# FAL65816_Audio.net
KiCad netlist of a schematic drawn in EAGLE
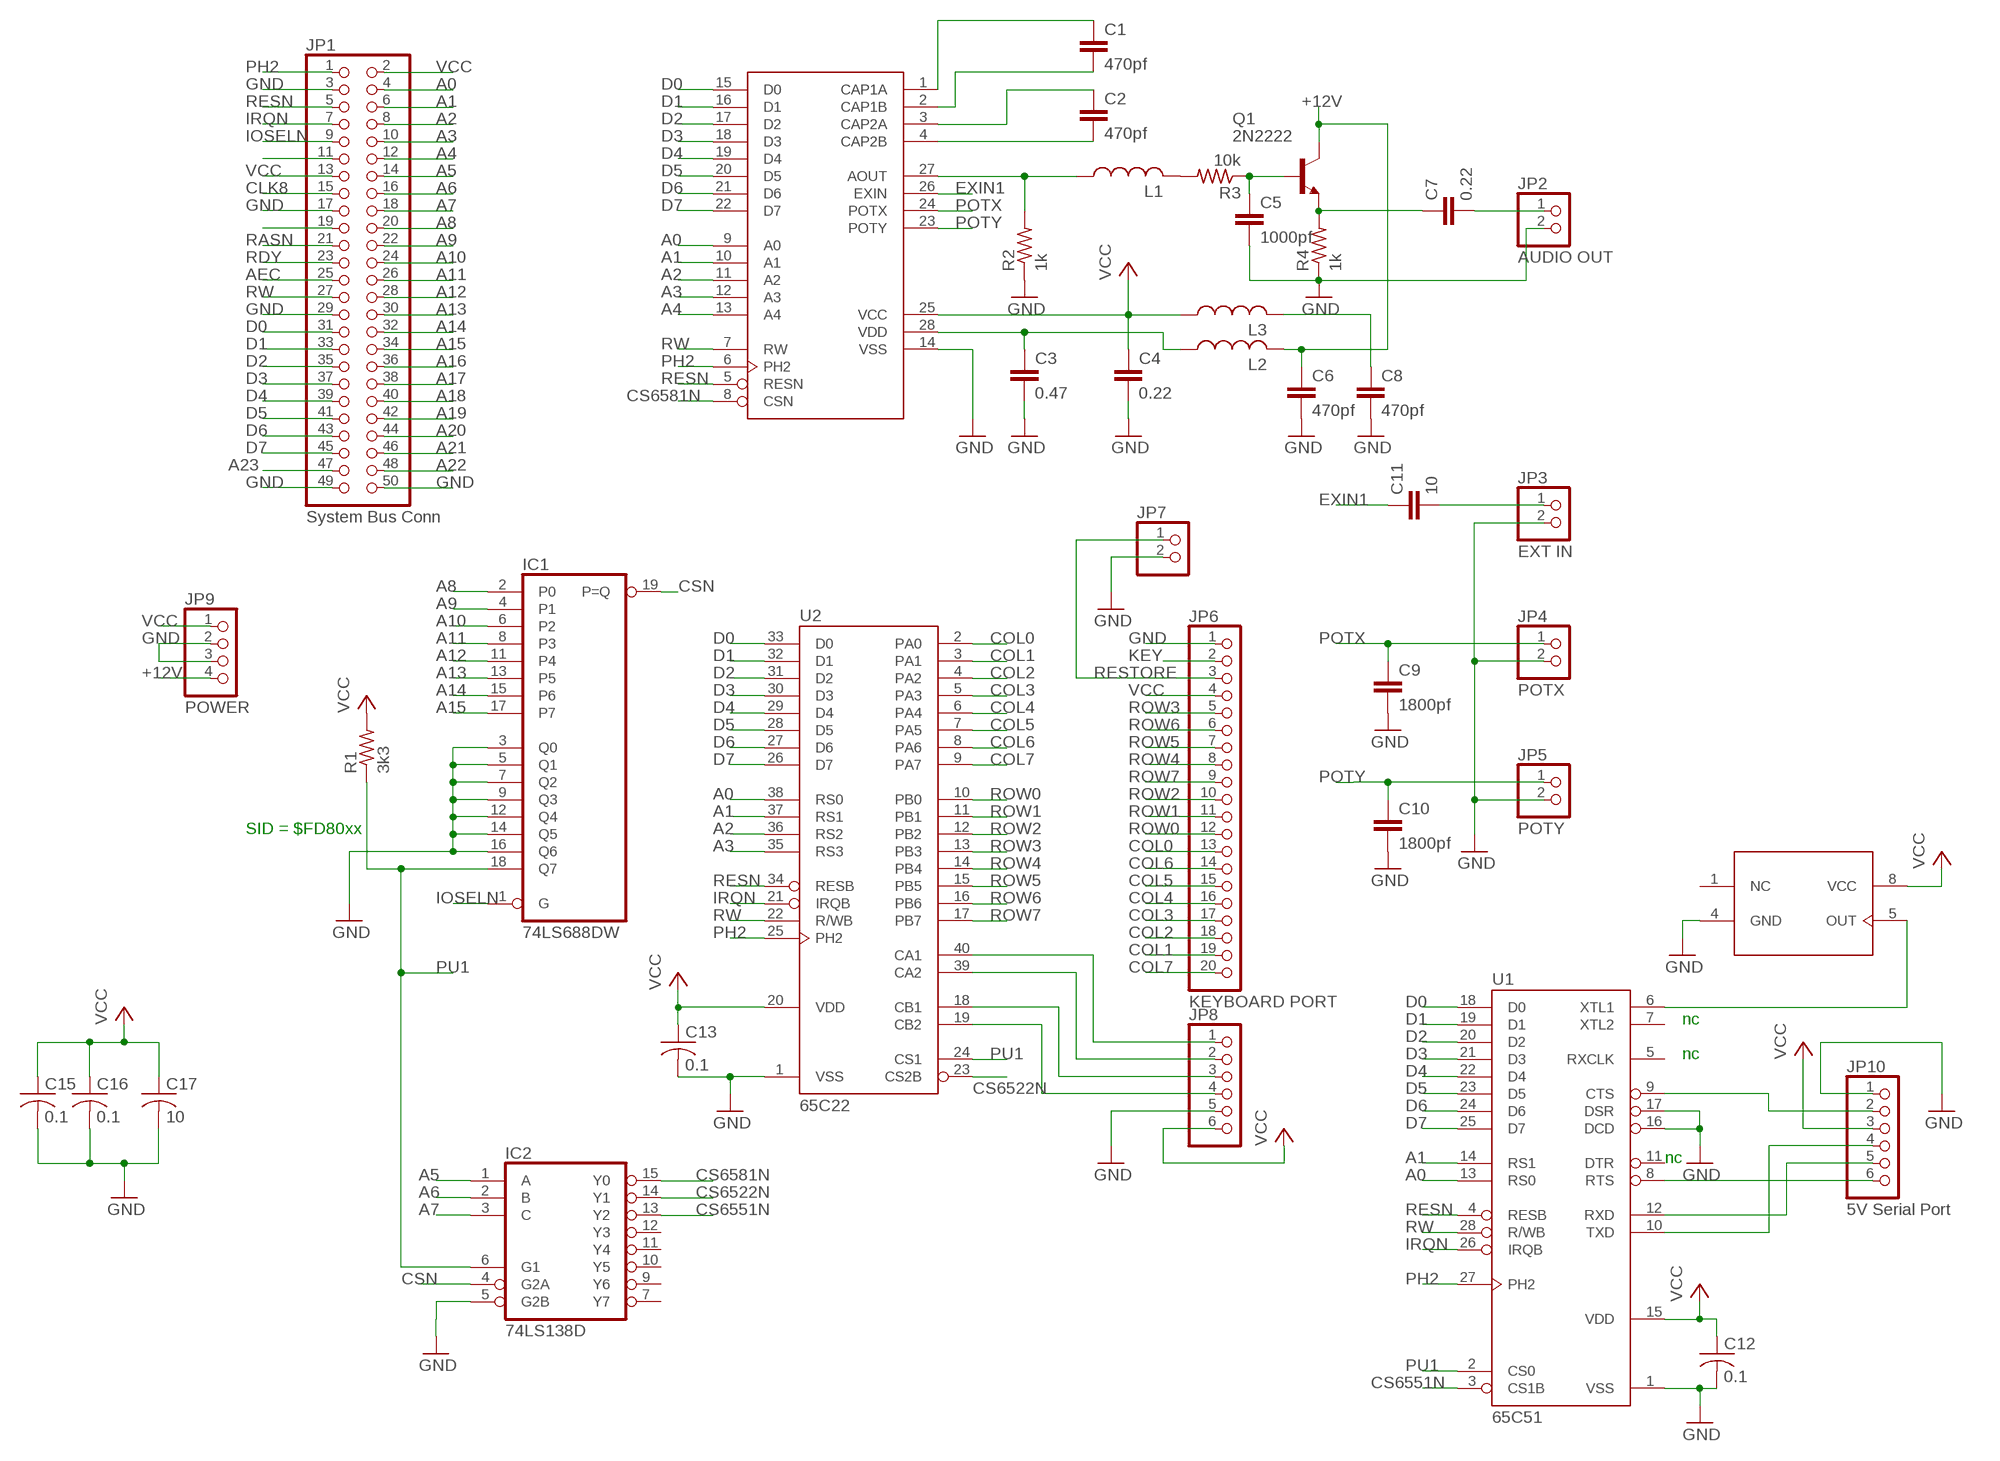
[diagram p0: schematic, sheet 1]

(export (version "E")
  (design (tool "Eeschema 10.0.6"))
  (components
    (comp (ref "C1")
      (value "470pf")
      (footprint "eagle-import:C050-024X044")
      (libsource (lib "eagle-import") (part "C-EU050-024X044"))
    )
    (comp (ref "C2")
      (value "470pf")
      (footprint "eagle-import:C050-024X044")
      (libsource (lib "eagle-import") (part "C-EU050-024X044"))
    )
    (comp (ref "C3")
      (value "0.47")
      (footprint "eagle-import:C050-024X044")
      (libsource (lib "eagle-import") (part "C-EU050-024X044"))
    )
    (comp (ref "C4")
      (value "0.22")
      (footprint "eagle-import:C050-024X044")
      (libsource (lib "eagle-import") (part "C-EU050-024X044"))
    )
    (comp (ref "C5")
      (value "1000pf")
      (footprint "eagle-import:C050-024X044")
      (libsource (lib "eagle-import") (part "C-EU050-024X044"))
    )
    (comp (ref "C6")
      (value "470pf")
      (footprint "eagle-import:C050-024X044")
      (libsource (lib "eagle-import") (part "C-EU050-024X044"))
    )
    (comp (ref "C7")
      (value "0.22")
      (footprint "eagle-import:C050-024X044")
      (libsource (lib "eagle-import") (part "C-EU050-024X044"))
    )
    (comp (ref "C8")
      (value "470pf")
      (footprint "eagle-import:C050-024X044")
      (libsource (lib "eagle-import") (part "C-EU050-024X044"))
    )
    (comp (ref "C9")
      (value "1800pf")
      (footprint "eagle-import:C050-024X044")
      (libsource (lib "eagle-import") (part "C-EU050-024X044"))
    )
    (comp (ref "C10")
      (value "1800pf")
      (footprint "eagle-import:C050-024X044")
      (libsource (lib "eagle-import") (part "C-EU050-024X044"))
    )
    (comp (ref "C11")
      (value "10")
      (footprint "eagle-import:C050-024X044")
      (libsource (lib "eagle-import") (part "C-EU050-024X044"))
    )
    (comp (ref "C12")
      (value "0.1")
      (footprint "eagle-import:C050-024X044")
      (libsource (lib "eagle-import") (part "C-US050-024X044"))
    )
    (comp (ref "C13")
      (value "0.1")
      (footprint "eagle-import:C050-024X044")
      (libsource (lib "eagle-import") (part "C-US050-024X044"))
    )
    (comp (ref "C15")
      (value "0.1")
      (footprint "eagle-import:C050-024X044")
      (libsource (lib "eagle-import") (part "C-US050-024X044"))
    )
    (comp (ref "C16")
      (value "0.1")
      (footprint "eagle-import:C050-024X044")
      (libsource (lib "eagle-import") (part "C-US050-024X044"))
    )
    (comp (ref "C17")
      (value "10")
      (footprint "eagle-import:C050-024X044")
      (libsource (lib "eagle-import") (part "C-US050-024X044"))
    )
    (comp (ref "IC1")
      (value "74LS688DW")
      (footprint "eagle-import:SO20W")
      (libsource (lib "eagle-import") (part "74688DWLS"))
    )
    (comp (ref "IC2")
      (value "74LS138D")
      (footprint "eagle-import:SO16")
      (libsource (lib "eagle-import") (part "74138DLS"))
    )
    (comp (ref "JP1")
      (value "System Bus Conn")
      (footprint "eagle-import:2X25_90")
      (libsource (lib "eagle-import") (part "PINHD-2X25/90"))
    )
    (comp (ref "JP2")
      (value "AUDIO OUT")
      (footprint "eagle-import:1X02")
      (libsource (lib "eagle-import") (part "PINHD-1X2"))
    )
    (comp (ref "JP3")
      (value "EXT IN")
      (footprint "eagle-import:1X02")
      (libsource (lib "eagle-import") (part "PINHD-1X2"))
    )
    (comp (ref "JP4")
      (value "POTX")
      (footprint "eagle-import:1X02")
      (libsource (lib "eagle-import") (part "PINHD-1X2"))
    )
    (comp (ref "JP5")
      (value "POTY")
      (footprint "eagle-import:1X02")
      (libsource (lib "eagle-import") (part "PINHD-1X2"))
    )
    (comp (ref "JP6")
      (value "KEYBOARD PORT")
      (footprint "eagle-import:1X20")
      (libsource (lib "eagle-import") (part "PINHD-1X20"))
    )
    (comp (ref "JP7")
      (value "PINHD-1X2")
      (footprint "eagle-import:1X02")
      (libsource (lib "eagle-import") (part "PINHD-1X2"))
    )
    (comp (ref "JP8")
      (value "PINHD-1X6/90")
      (footprint "eagle-import:1X06_90")
      (libsource (lib "eagle-import") (part "PINHD-1X6/90"))
    )
    (comp (ref "JP9")
      (value "POWER")
      (footprint "eagle-import:1X04_90")
      (libsource (lib "eagle-import") (part "PINHD-1X4/90"))
    )
    (comp (ref "JP10")
      (value "5V Serial Port")
      (footprint "eagle-import:1X06_90")
      (libsource (lib "eagle-import") (part "PINHD-1X6/90"))
    )
    (comp (ref "L1")
      (value "L-US0204/7")
      (footprint "eagle-import:0204_7")
      (libsource (lib "eagle-import") (part "L-US0204/7"))
    )
    (comp (ref "L2")
      (value "L-US0204/7")
      (footprint "eagle-import:0204_7")
      (libsource (lib "eagle-import") (part "L-US0204/7"))
    )
    (comp (ref "L3")
      (value "L-US0204/7")
      (footprint "eagle-import:0204_7")
      (libsource (lib "eagle-import") (part "L-US0204/7"))
    )
    (comp (ref "Q1")
      (value "2N2222")
      (footprint "eagle-import:TO18")
      (libsource (lib "eagle-import") (part "2N2222"))
    )
    (comp (ref "R1")
      (value "3k3")
      (footprint "eagle-import:0204_7")
      (libsource (lib "eagle-import") (part "R-US_0204/7"))
    )
    (comp (ref "R2")
      (value "1k")
      (footprint "eagle-import:0204_7")
      (libsource (lib "eagle-import") (part "R-US_0204/7"))
    )
    (comp (ref "R3")
      (value "10k")
      (footprint "eagle-import:0204_7")
      (libsource (lib "eagle-import") (part "R-US_0204/7"))
    )
    (comp (ref "R4")
      (value "1k")
      (footprint "eagle-import:0204_7")
      (libsource (lib "eagle-import") (part "R-US_0204/7"))
    )
    (comp (ref "U$1")
      (value "6581")
      (footprint "eagle-import:DIP-28")
      (libsource (lib "eagle-import") (part "FT6581"))
    )
    (comp (ref "U$2")
      (value "OSC")
      (footprint "eagle-import:DIL08")
      (libsource (lib "eagle-import") (part "OSC"))
    )
    (comp (ref "U1")
      (value "65C51")
      (footprint "eagle-import:DIP-28")
      (libsource (lib "eagle-import") (part "G65SC51P"))
    )
    (comp (ref "U2")
      (value "65C22")
      (footprint "eagle-import:DIP-40")
      (libsource (lib "eagle-import") (part "G65SC22P"))
    )
  )
  (nets
    (net (code "1") (name "/+12V") (class "Default")
      (node (ref "C6") (pin "1") (pinfunction "1_1") (pintype "passive"))
      (node (ref "JP9") (pin "4") (pinfunction "4_4") (pintype "passive"))
      (node (ref "L2") (pin "2") (pinfunction "2_2") (pintype "passive"))
      (node (ref "Q1") (pin "3") (pinfunction "C_3") (pintype "passive"))
    )
    (net (code "2") (name "/A0") (class "Default")
      (node (ref "JP1") (pin "4") (pinfunction "4_4") (pintype "passive"))
      (node (ref "U$1") (pin "9") (pinfunction "A0_9") (pintype "input"))
      (node (ref "U1") (pin "13") (pinfunction "RS0_13") (pintype "input"))
      (node (ref "U2") (pin "38") (pinfunction "RS0_38") (pintype "input"))
    )
    (net (code "3") (name "/A1") (class "Default")
      (node (ref "JP1") (pin "6") (pinfunction "6_6") (pintype "passive"))
      (node (ref "U$1") (pin "10") (pinfunction "A1_10") (pintype "input"))
      (node (ref "U1") (pin "14") (pinfunction "RS1_14") (pintype "input"))
      (node (ref "U2") (pin "37") (pinfunction "RS1_37") (pintype "input"))
    )
    (net (code "4") (name "/A2") (class "Default")
      (node (ref "JP1") (pin "8") (pinfunction "8_8") (pintype "passive"))
      (node (ref "U$1") (pin "11") (pinfunction "A2_11") (pintype "input"))
      (node (ref "U2") (pin "36") (pinfunction "RS2_36") (pintype "input"))
    )
    (net (code "5") (name "/A3") (class "Default")
      (node (ref "JP1") (pin "10") (pinfunction "10_10") (pintype "passive"))
      (node (ref "U$1") (pin "12") (pinfunction "A3_12") (pintype "input"))
      (node (ref "U2") (pin "35") (pinfunction "RS3_35") (pintype "input"))
    )
    (net (code "6") (name "/A4") (class "Default")
      (node (ref "JP1") (pin "12") (pinfunction "12_12") (pintype "passive"))
      (node (ref "U$1") (pin "13") (pinfunction "A4_13") (pintype "input"))
    )
    (net (code "7") (name "/A5") (class "Default")
      (node (ref "IC2") (pin "1") (pinfunction "A_1") (pintype "input"))
      (node (ref "JP1") (pin "14") (pinfunction "14_14") (pintype "passive"))
    )
    (net (code "8") (name "/A6") (class "Default")
      (node (ref "IC2") (pin "2") (pinfunction "B_2") (pintype "input"))
      (node (ref "JP1") (pin "16") (pinfunction "16_16") (pintype "passive"))
    )
    (net (code "9") (name "/A7") (class "Default")
      (node (ref "IC2") (pin "3") (pinfunction "C_3") (pintype "input"))
      (node (ref "JP1") (pin "18") (pinfunction "18_18") (pintype "passive"))
    )
    (net (code "10") (name "/A8") (class "Default")
      (node (ref "IC1") (pin "2") (pinfunction "P0_2") (pintype "input"))
      (node (ref "JP1") (pin "20") (pinfunction "20_20") (pintype "passive"))
    )
    (net (code "11") (name "/A9") (class "Default")
      (node (ref "IC1") (pin "4") (pinfunction "P1_4") (pintype "input"))
      (node (ref "JP1") (pin "22") (pinfunction "22_22") (pintype "passive"))
    )
    (net (code "12") (name "/A10") (class "Default")
      (node (ref "IC1") (pin "6") (pinfunction "P2_6") (pintype "input"))
      (node (ref "JP1") (pin "24") (pinfunction "24_24") (pintype "passive"))
    )
    (net (code "13") (name "/A11") (class "Default")
      (node (ref "IC1") (pin "8") (pinfunction "P3_8") (pintype "input"))
      (node (ref "JP1") (pin "26") (pinfunction "26_26") (pintype "passive"))
    )
    (net (code "14") (name "/A12") (class "Default")
      (node (ref "IC1") (pin "11") (pinfunction "P4_11") (pintype "input"))
      (node (ref "JP1") (pin "28") (pinfunction "28_28") (pintype "passive"))
    )
    (net (code "15") (name "/A13") (class "Default")
      (node (ref "IC1") (pin "13") (pinfunction "P5_13") (pintype "input"))
      (node (ref "JP1") (pin "30") (pinfunction "30_30") (pintype "passive"))
    )
    (net (code "16") (name "/A14") (class "Default")
      (node (ref "IC1") (pin "15") (pinfunction "P6_15") (pintype "input"))
      (node (ref "JP1") (pin "32") (pinfunction "32_32") (pintype "passive"))
    )
    (net (code "17") (name "/A15") (class "Default")
      (node (ref "IC1") (pin "17") (pinfunction "P7_17") (pintype "input"))
      (node (ref "JP1") (pin "34") (pinfunction "34_34") (pintype "passive"))
    )
    (net (code "18") (name "/A16") (class "Default")
      (node (ref "JP1") (pin "36") (pinfunction "36_36") (pintype "passive"))
    )
    (net (code "19") (name "/A17") (class "Default")
      (node (ref "JP1") (pin "38") (pinfunction "38_38") (pintype "passive"))
    )
    (net (code "20") (name "/A18") (class "Default")
      (node (ref "JP1") (pin "40") (pinfunction "40_40") (pintype "passive"))
    )
    (net (code "21") (name "/A19") (class "Default")
      (node (ref "JP1") (pin "42") (pinfunction "42_42") (pintype "passive"))
    )
    (net (code "22") (name "/A20") (class "Default")
      (node (ref "JP1") (pin "44") (pinfunction "44_44") (pintype "passive"))
    )
    (net (code "23") (name "/A21") (class "Default")
      (node (ref "JP1") (pin "46") (pinfunction "46_46") (pintype "passive"))
    )
    (net (code "24") (name "/A22") (class "Default")
      (node (ref "JP1") (pin "48") (pinfunction "48_48") (pintype "passive"))
    )
    (net (code "25") (name "/A23") (class "Default")
      (node (ref "JP1") (pin "47") (pinfunction "47_47") (pintype "passive"))
    )
    (net (code "26") (name "/AEC") (class "Default")
      (node (ref "JP1") (pin "25") (pinfunction "25_25") (pintype "passive"))
    )
    (net (code "27") (name "/CLK8") (class "Default")
      (node (ref "JP1") (pin "15") (pinfunction "15_15") (pintype "passive"))
    )
    (net (code "28") (name "/COL0") (class "Default")
      (node (ref "JP6") (pin "13") (pinfunction "13_13") (pintype "passive"))
      (node (ref "U2") (pin "2") (pinfunction "PA0_2") (pintype "bidirectional"))
    )
    (net (code "29") (name "/COL1") (class "Default")
      (node (ref "JP6") (pin "19") (pinfunction "19_19") (pintype "passive"))
      (node (ref "U2") (pin "3") (pinfunction "PA1_3") (pintype "bidirectional"))
    )
    (net (code "30") (name "/COL2") (class "Default")
      (node (ref "JP6") (pin "18") (pinfunction "18_18") (pintype "passive"))
      (node (ref "U2") (pin "4") (pinfunction "PA2_4") (pintype "bidirectional"))
    )
    (net (code "31") (name "/COL3") (class "Default")
      (node (ref "JP6") (pin "17") (pinfunction "17_17") (pintype "passive"))
      (node (ref "U2") (pin "5") (pinfunction "PA3_5") (pintype "bidirectional"))
    )
    (net (code "32") (name "/COL4") (class "Default")
      (node (ref "JP6") (pin "16") (pinfunction "16_16") (pintype "passive"))
      (node (ref "U2") (pin "6") (pinfunction "PA4_6") (pintype "bidirectional"))
    )
    (net (code "33") (name "/COL5") (class "Default")
      (node (ref "JP6") (pin "15") (pinfunction "15_15") (pintype "passive"))
      (node (ref "U2") (pin "7") (pinfunction "PA5_7") (pintype "bidirectional"))
    )
    (net (code "34") (name "/COL6") (class "Default")
      (node (ref "JP6") (pin "14") (pinfunction "14_14") (pintype "passive"))
      (node (ref "U2") (pin "8") (pinfunction "PA6_8") (pintype "bidirectional"))
    )
    (net (code "35") (name "/COL7") (class "Default")
      (node (ref "JP6") (pin "20") (pinfunction "20_20") (pintype "passive"))
      (node (ref "U2") (pin "9") (pinfunction "PA7_9") (pintype "bidirectional"))
    )
    (net (code "36") (name "/CS6522N") (class "Default")
      (node (ref "IC2") (pin "14") (pinfunction "Y1_14") (pintype "output"))
      (node (ref "U2") (pin "23") (pinfunction "CS2B_23") (pintype "input"))
    )
    (net (code "37") (name "/CS6551N") (class "Default")
      (node (ref "IC2") (pin "13") (pinfunction "Y2_13") (pintype "output"))
      (node (ref "U1") (pin "3") (pinfunction "CS1B_3") (pintype "input"))
    )
    (net (code "38") (name "/CS6581N") (class "Default")
      (node (ref "IC2") (pin "15") (pinfunction "Y0_15") (pintype "output"))
      (node (ref "U$1") (pin "8") (pinfunction "CSN_8") (pintype "input"))
    )
    (net (code "39") (name "/CSN") (class "Default")
      (node (ref "IC1") (pin "19") (pinfunction "P=Q_19") (pintype "output"))
      (node (ref "IC2") (pin "4") (pinfunction "G2A_4") (pintype "input"))
    )
    (net (code "40") (name "/D0") (class "Default")
      (node (ref "JP1") (pin "31") (pinfunction "31_31") (pintype "passive"))
      (node (ref "U$1") (pin "15") (pinfunction "D0_15") (pintype "bidirectional"))
      (node (ref "U1") (pin "18") (pinfunction "D0_18") (pintype "bidirectional"))
      (node (ref "U2") (pin "33") (pinfunction "D0_33") (pintype "bidirectional"))
    )
    (net (code "41") (name "/D1") (class "Default")
      (node (ref "JP1") (pin "33") (pinfunction "33_33") (pintype "passive"))
      (node (ref "U$1") (pin "16") (pinfunction "D1_16") (pintype "bidirectional"))
      (node (ref "U1") (pin "19") (pinfunction "D1_19") (pintype "bidirectional"))
      (node (ref "U2") (pin "32") (pinfunction "D1_32") (pintype "bidirectional"))
    )
    (net (code "42") (name "/D2") (class "Default")
      (node (ref "JP1") (pin "35") (pinfunction "35_35") (pintype "passive"))
      (node (ref "U$1") (pin "17") (pinfunction "D2_17") (pintype "bidirectional"))
      (node (ref "U1") (pin "20") (pinfunction "D2_20") (pintype "bidirectional"))
      (node (ref "U2") (pin "31") (pinfunction "D2_31") (pintype "bidirectional"))
    )
    (net (code "43") (name "/D3") (class "Default")
      (node (ref "JP1") (pin "37") (pinfunction "37_37") (pintype "passive"))
      (node (ref "U$1") (pin "18") (pinfunction "D3_18") (pintype "bidirectional"))
      (node (ref "U1") (pin "21") (pinfunction "D3_21") (pintype "bidirectional"))
      (node (ref "U2") (pin "30") (pinfunction "D3_30") (pintype "bidirectional"))
    )
    (net (code "44") (name "/D4") (class "Default")
      (node (ref "JP1") (pin "39") (pinfunction "39_39") (pintype "passive"))
      (node (ref "U$1") (pin "19") (pinfunction "D4_19") (pintype "bidirectional"))
      (node (ref "U1") (pin "22") (pinfunction "D4_22") (pintype "bidirectional"))
      (node (ref "U2") (pin "29") (pinfunction "D4_29") (pintype "bidirectional"))
    )
    (net (code "45") (name "/D5") (class "Default")
      (node (ref "JP1") (pin "41") (pinfunction "41_41") (pintype "passive"))
      (node (ref "U$1") (pin "20") (pinfunction "D5_20") (pintype "bidirectional"))
      (node (ref "U1") (pin "23") (pinfunction "D5_23") (pintype "bidirectional"))
      (node (ref "U2") (pin "28") (pinfunction "D5_28") (pintype "bidirectional"))
    )
    (net (code "46") (name "/D6") (class "Default")
      (node (ref "JP1") (pin "43") (pinfunction "43_43") (pintype "passive"))
      (node (ref "U$1") (pin "21") (pinfunction "D6_21") (pintype "bidirectional"))
      (node (ref "U1") (pin "24") (pinfunction "D6_24") (pintype "bidirectional"))
      (node (ref "U2") (pin "27") (pinfunction "D6_27") (pintype "bidirectional"))
    )
    (net (code "47") (name "/D7") (class "Default")
      (node (ref "JP1") (pin "45") (pinfunction "45_45") (pintype "passive"))
      (node (ref "U$1") (pin "22") (pinfunction "D7_22") (pintype "bidirectional"))
      (node (ref "U1") (pin "25") (pinfunction "D7_25") (pintype "bidirectional"))
      (node (ref "U2") (pin "26") (pinfunction "D7_26") (pintype "bidirectional"))
    )
    (net (code "48") (name "/EXIN1") (class "Default")
      (node (ref "C11") (pin "1") (pinfunction "1_1") (pintype "passive"))
      (node (ref "U$1") (pin "26") (pinfunction "EXIN_26") (pintype "input"))
    )
    (net (code "49") (name "/IOSELN") (class "Default")
      (node (ref "IC1") (pin "1") (pinfunction "G_1") (pintype "input"))
      (node (ref "JP1") (pin "9") (pinfunction "9_9") (pintype "passive"))
    )
    (net (code "50") (name "/IRQN") (class "Default")
      (node (ref "JP1") (pin "7") (pinfunction "7_7") (pintype "passive"))
      (node (ref "U1") (pin "26") (pinfunction "IRQB_26") (pintype "output"))
      (node (ref "U2") (pin "21") (pinfunction "IRQB_21") (pintype "output"))
    )
    (net (code "51") (name "/KEY") (class "Default")
      (node (ref "JP6") (pin "2") (pinfunction "2_2") (pintype "passive"))
    )
    (net (code "52") (name "/PH2") (class "Default")
      (node (ref "JP1") (pin "1") (pinfunction "1_1") (pintype "passive"))
      (node (ref "U$1") (pin "6") (pinfunction "PH2_6") (pintype "input"))
      (node (ref "U1") (pin "27") (pinfunction "PH2_27") (pintype "power_in"))
      (node (ref "U2") (pin "25") (pinfunction "PH2_25") (pintype "input"))
    )
    (net (code "53") (name "/POTX") (class "Default")
      (node (ref "C9") (pin "1") (pinfunction "1_1") (pintype "passive"))
      (node (ref "JP4") (pin "1") (pinfunction "1_1") (pintype "passive"))
      (node (ref "U$1") (pin "24") (pinfunction "POTX_24") (pintype "input"))
    )
    (net (code "54") (name "/POTY") (class "Default")
      (node (ref "C10") (pin "1") (pinfunction "1_1") (pintype "passive"))
      (node (ref "JP5") (pin "1") (pinfunction "1_1") (pintype "passive"))
      (node (ref "U$1") (pin "23") (pinfunction "POTY_23") (pintype "input"))
    )
    (net (code "55") (name "/PU1") (class "Default")
      (node (ref "IC1") (pin "18") (pinfunction "Q7_18") (pintype "input"))
      (node (ref "IC2") (pin "6") (pinfunction "G1_6") (pintype "input"))
      (node (ref "R1") (pin "1") (pinfunction "1_1") (pintype "passive"))
      (node (ref "U1") (pin "2") (pinfunction "CS0_2") (pintype "input"))
      (node (ref "U2") (pin "24") (pinfunction "CS1_24") (pintype "input"))
    )
    (net (code "56") (name "/RASN") (class "Default")
      (node (ref "JP1") (pin "21") (pinfunction "21_21") (pintype "passive"))
    )
    (net (code "57") (name "/RDY") (class "Default")
      (node (ref "JP1") (pin "23") (pinfunction "23_23") (pintype "passive"))
    )
    (net (code "58") (name "/RESN") (class "Default")
      (node (ref "JP1") (pin "5") (pinfunction "5_5") (pintype "passive"))
      (node (ref "U$1") (pin "5") (pinfunction "RESN_5") (pintype "input"))
      (node (ref "U1") (pin "4") (pinfunction "RESB_4") (pintype "input"))
      (node (ref "U2") (pin "34") (pinfunction "RESB_34") (pintype "input"))
    )
    (net (code "59") (name "/RESTORE") (class "Default")
      (node (ref "JP6") (pin "3") (pinfunction "3_3") (pintype "passive"))
      (node (ref "JP7") (pin "1") (pinfunction "1_1") (pintype "passive"))
    )
    (net (code "60") (name "/ROW0") (class "Default")
      (node (ref "JP6") (pin "12") (pinfunction "12_12") (pintype "passive"))
      (node (ref "U2") (pin "10") (pinfunction "PB0_10") (pintype "bidirectional"))
    )
    (net (code "61") (name "/ROW1") (class "Default")
      (node (ref "JP6") (pin "11") (pinfunction "11_11") (pintype "passive"))
      (node (ref "U2") (pin "11") (pinfunction "PB1_11") (pintype "bidirectional"))
    )
    (net (code "62") (name "/ROW2") (class "Default")
      (node (ref "JP6") (pin "10") (pinfunction "10_10") (pintype "passive"))
      (node (ref "U2") (pin "12") (pinfunction "PB2_12") (pintype "bidirectional"))
    )
    (net (code "63") (name "/ROW3") (class "Default")
      (node (ref "JP6") (pin "5") (pinfunction "5_5") (pintype "passive"))
      (node (ref "U2") (pin "13") (pinfunction "PB3_13") (pintype "bidirectional"))
    )
    (net (code "64") (name "/ROW4") (class "Default")
      (node (ref "JP6") (pin "8") (pinfunction "8_8") (pintype "passive"))
      (node (ref "U2") (pin "14") (pinfunction "PB4_14") (pintype "bidirectional"))
    )
    (net (code "65") (name "/ROW5") (class "Default")
      (node (ref "JP6") (pin "7") (pinfunction "7_7") (pintype "passive"))
      (node (ref "U2") (pin "15") (pinfunction "PB5_15") (pintype "bidirectional"))
    )
    (net (code "66") (name "/ROW6") (class "Default")
      (node (ref "JP6") (pin "6") (pinfunction "6_6") (pintype "passive"))
      (node (ref "U2") (pin "16") (pinfunction "PB6_16") (pintype "bidirectional"))
    )
    (net (code "67") (name "/ROW7") (class "Default")
      (node (ref "JP6") (pin "9") (pinfunction "9_9") (pintype "passive"))
      (node (ref "U2") (pin "17") (pinfunction "PB7_17") (pintype "bidirectional"))
    )
    (net (code "68") (name "/RW") (class "Default")
      (node (ref "JP1") (pin "27") (pinfunction "27_27") (pintype "passive"))
      (node (ref "U$1") (pin "7") (pinfunction "RW_7") (pintype "input"))
      (node (ref "U1") (pin "28") (pinfunction "R/WB_28") (pintype "input"))
      (node (ref "U2") (pin "22") (pinfunction "R/WB_22") (pintype "input"))
    )
    (net (code "69") (name "GND") (class "Default")
      (node (ref "C10") (pin "2") (pinfunction "2_2") (pintype "passive"))
      (node (ref "C12") (pin "2") (pinfunction "2_2") (pintype "passive"))
      (node (ref "C13") (pin "2") (pinfunction "2_2") (pintype "passive"))
      (node (ref "C15") (pin "2") (pinfunction "2_2") (pintype "passive"))
      (node (ref "C16") (pin "2") (pinfunction "2_2") (pintype "passive"))
      (node (ref "C17") (pin "2") (pinfunction "2_2") (pintype "passive"))
      (node (ref "C3") (pin "2") (pinfunction "2_2") (pintype "passive"))
      (node (ref "C4") (pin "2") (pinfunction "2_2") (pintype "passive"))
      (node (ref "C5") (pin "2") (pinfunction "2_2") (pintype "passive"))
      (node (ref "C6") (pin "2") (pinfunction "2_2") (pintype "passive"))
      (node (ref "C8") (pin "2") (pinfunction "2_2") (pintype "passive"))
      (node (ref "C9") (pin "2") (pinfunction "2_2") (pintype "passive"))
      (node (ref "IC1") (pin "12") (pinfunction "Q4_12") (pintype "input"))
      (node (ref "IC1") (pin "14") (pinfunction "Q5_14") (pintype "input"))
      (node (ref "IC1") (pin "16") (pinfunction "Q6_16") (pintype "input"))
      (node (ref "IC1") (pin "3") (pinfunction "Q0_3") (pintype "input"))
      (node (ref "IC1") (pin "5") (pinfunction "Q1_5") (pintype "input"))
      (node (ref "IC1") (pin "7") (pinfunction "Q2_7") (pintype "input"))
      (node (ref "IC1") (pin "9") (pinfunction "Q3_9") (pintype "input"))
      (node (ref "IC2") (pin "5") (pinfunction "G2B_5") (pintype "input"))
      (node (ref "JP1") (pin "17") (pinfunction "17_17") (pintype "passive"))
      (node (ref "JP1") (pin "29") (pinfunction "29_29") (pintype "passive"))
      (node (ref "JP1") (pin "3") (pinfunction "3_3") (pintype "passive"))
      (node (ref "JP1") (pin "49") (pinfunction "49_49") (pintype "passive"))
      (node (ref "JP1") (pin "50") (pinfunction "50_50") (pintype "passive"))
      (node (ref "JP10") (pin "1") (pinfunction "1_1") (pintype "passive"))
      (node (ref "JP2") (pin "2") (pinfunction "2_2") (pintype "passive"))
      (node (ref "JP3") (pin "2") (pinfunction "2_2") (pintype "passive"))
      (node (ref "JP4") (pin "2") (pinfunction "2_2") (pintype "passive"))
      (node (ref "JP5") (pin "2") (pinfunction "2_2") (pintype "passive"))
      (node (ref "JP6") (pin "1") (pinfunction "1_1") (pintype "passive"))
      (node (ref "JP7") (pin "2") (pinfunction "2_2") (pintype "passive"))
      (node (ref "JP8") (pin "5") (pinfunction "5_5") (pintype "passive"))
      (node (ref "JP9") (pin "2") (pinfunction "2_2") (pintype "passive"))
      (node (ref "JP9") (pin "3") (pinfunction "3_3") (pintype "passive"))
      (node (ref "R2") (pin "1") (pinfunction "1_1") (pintype "passive"))
      (node (ref "R4") (pin "1") (pinfunction "1_1") (pintype "passive"))
      (node (ref "U$1") (pin "14") (pinfunction "VSS_14") (pintype "power_in"))
      (node (ref "U$2") (pin "4") (pinfunction "GND_4") (pintype "power_in"))
      (node (ref "U1") (pin "1") (pinfunction "VSS_1") (pintype "power_in"))
      (node (ref "U1") (pin "16") (pinfunction "DCD_16") (pintype "input"))
      (node (ref "U1") (pin "17") (pinfunction "DSR_17") (pintype "input"))
      (node (ref "U2") (pin "1") (pinfunction "VSS_1") (pintype "power_in"))
    )
    (net (code "70") (name "Net-(C7-Pad2)") (class "Default")
      (node (ref "C7") (pin "2") (pinfunction "2_2") (pintype "passive"))
      (node (ref "JP2") (pin "1") (pinfunction "1_1") (pintype "passive"))
    )
    (net (code "71") (name "Net-(C8-Pad1)") (class "Default")
      (node (ref "C8") (pin "1") (pinfunction "1_1") (pintype "passive"))
      (node (ref "L3") (pin "2") (pinfunction "2_2") (pintype "passive"))
    )
    (net (code "72") (name "Net-(C11-Pad2)") (class "Default")
      (node (ref "C11") (pin "2") (pinfunction "2_2") (pintype "passive"))
      (node (ref "JP3") (pin "1") (pinfunction "1_1") (pintype "passive"))
    )
    (net (code "73") (name "Net-(L1-Pad2)") (class "Default")
      (node (ref "L1") (pin "2") (pinfunction "2_2") (pintype "passive"))
      (node (ref "R3") (pin "2") (pinfunction "2_2") (pintype "passive"))
    )
    (net (code "74") (name "Net-(Q1-B)") (class "Default")
      (node (ref "C5") (pin "1") (pinfunction "1_1") (pintype "passive"))
      (node (ref "Q1") (pin "2") (pinfunction "B_2") (pintype "passive"))
      (node (ref "R3") (pin "1") (pinfunction "1_1") (pintype "passive"))
    )
    (net (code "75") (name "Net-(Q1-E)") (class "Default")
      (node (ref "C7") (pin "1") (pinfunction "1_1") (pintype "passive"))
      (node (ref "Q1") (pin "1") (pinfunction "E_1") (pintype "passive"))
      (node (ref "R4") (pin "2") (pinfunction "2_2") (pintype "passive"))
    )
    (net (code "76") (name "Net-(U$1-AOUT)") (class "Default")
      (node (ref "L1") (pin "1") (pinfunction "1_1") (pintype "passive"))
      (node (ref "R2") (pin "2") (pinfunction "2_2") (pintype "passive"))
      (node (ref "U$1") (pin "27") (pinfunction "AOUT_27") (pintype "output"))
    )
    (net (code "77") (name "Net-(U$1-CAP1A)") (class "Default")
      (node (ref "C1") (pin "1") (pinfunction "1_1") (pintype "passive"))
      (node (ref "U$1") (pin "1") (pinfunction "CAP1A_1") (pintype "bidirectional"))
    )
    (net (code "78") (name "Net-(U$1-CAP1B)") (class "Default")
      (node (ref "C1") (pin "2") (pinfunction "2_2") (pintype "passive"))
      (node (ref "U$1") (pin "2") (pinfunction "CAP1B_2") (pintype "bidirectional"))
    )
    (net (code "79") (name "Net-(U$1-CAP2A)") (class "Default")
      (node (ref "C2") (pin "1") (pinfunction "1_1") (pintype "passive"))
      (node (ref "U$1") (pin "3") (pinfunction "CAP2A_3") (pintype "bidirectional"))
    )
    (net (code "80") (name "Net-(U$1-CAP2B)") (class "Default")
      (node (ref "C2") (pin "2") (pinfunction "2_2") (pintype "passive"))
      (node (ref "U$1") (pin "4") (pinfunction "CAP2B_4") (pintype "bidirectional"))
    )
    (net (code "81") (name "Net-(U$1-VDD)") (class "Default")
      (node (ref "C3") (pin "1") (pinfunction "1_1") (pintype "passive"))
      (node (ref "L2") (pin "1") (pinfunction "1_1") (pintype "passive"))
      (node (ref "U$1") (pin "28") (pinfunction "VDD_28") (pintype "power_in"))
    )
    (net (code "82") (name "Net-(U$2-OUT)") (class "Default")
      (node (ref "U$2") (pin "5") (pinfunction "OUT_5") (pintype "output"))
      (node (ref "U1") (pin "6") (pinfunction "XTL1_6") (pintype "input"))
    )
    (net (code "83") (name "Net-(U1-CTS)") (class "Default")
      (node (ref "JP10") (pin "2") (pinfunction "2_2") (pintype "passive"))
      (node (ref "U1") (pin "9") (pinfunction "CTS_9") (pintype "input"))
    )
    (net (code "84") (name "Net-(U1-RTS)") (class "Default")
      (node (ref "JP10") (pin "6") (pinfunction "6_6") (pintype "passive"))
      (node (ref "U1") (pin "8") (pinfunction "RTS_8") (pintype "output"))
    )
    (net (code "85") (name "Net-(U1-RXD)") (class "Default")
      (node (ref "JP10") (pin "5") (pinfunction "5_5") (pintype "passive"))
      (node (ref "U1") (pin "12") (pinfunction "RXD_12") (pintype "input"))
    )
    (net (code "86") (name "Net-(U1-TXD)") (class "Default")
      (node (ref "JP10") (pin "4") (pinfunction "4_4") (pintype "passive"))
      (node (ref "U1") (pin "10") (pinfunction "TXD_10") (pintype "output"))
    )
    (net (code "87") (name "Net-(U2-CA1)") (class "Default")
      (node (ref "JP8") (pin "1") (pinfunction "1_1") (pintype "passive"))
      (node (ref "U2") (pin "40") (pinfunction "CA1_40") (pintype "bidirectional"))
    )
    (net (code "88") (name "Net-(U2-CA2)") (class "Default")
      (node (ref "JP8") (pin "2") (pinfunction "2_2") (pintype "passive"))
      (node (ref "U2") (pin "39") (pinfunction "CA2_39") (pintype "bidirectional"))
    )
    (net (code "89") (name "Net-(U2-CB1)") (class "Default")
      (node (ref "JP8") (pin "3") (pinfunction "3_3") (pintype "passive"))
      (node (ref "U2") (pin "18") (pinfunction "CB1_18") (pintype "bidirectional"))
    )
    (net (code "90") (name "Net-(U2-CB2)") (class "Default")
      (node (ref "JP8") (pin "4") (pinfunction "4_4") (pintype "passive"))
      (node (ref "U2") (pin "19") (pinfunction "CB2_19") (pintype "bidirectional"))
    )
    (net (code "91") (name "VCC") (class "Default")
      (node (ref "C12") (pin "1") (pinfunction "1_1") (pintype "passive"))
      (node (ref "C13") (pin "1") (pinfunction "1_1") (pintype "passive"))
      (node (ref "C15") (pin "1") (pinfunction "1_1") (pintype "passive"))
      (node (ref "C16") (pin "1") (pinfunction "1_1") (pintype "passive"))
      (node (ref "C17") (pin "1") (pinfunction "1_1") (pintype "passive"))
      (node (ref "C4") (pin "1") (pinfunction "1_1") (pintype "passive"))
      (node (ref "JP1") (pin "13") (pinfunction "13_13") (pintype "passive"))
      (node (ref "JP1") (pin "2") (pinfunction "2_2") (pintype "passive"))
      (node (ref "JP10") (pin "3") (pinfunction "3_3") (pintype "passive"))
      (node (ref "JP6") (pin "4") (pinfunction "4_4") (pintype "passive"))
      (node (ref "JP8") (pin "6") (pinfunction "6_6") (pintype "passive"))
      (node (ref "JP9") (pin "1") (pinfunction "1_1") (pintype "passive"))
      (node (ref "L3") (pin "1") (pinfunction "1_1") (pintype "passive"))
      (node (ref "R1") (pin "2") (pinfunction "2_2") (pintype "passive"))
      (node (ref "U$1") (pin "25") (pinfunction "VCC_25") (pintype "power_in"))
      (node (ref "U$2") (pin "8") (pinfunction "VCC_8") (pintype "power_in"))
      (node (ref "U1") (pin "15") (pinfunction "VDD_15") (pintype "power_in"))
      (node (ref "U2") (pin "20") (pinfunction "VDD_20") (pintype "power_in"))
    )
    (net (code "92") (name "unconnected-(IC2A-Y3-Pad12)") (class "Default")
      (node (ref "IC2") (pin "12") (pinfunction "Y3_12") (pintype "output"))
    )
    (net (code "93") (name "unconnected-(IC2A-Y4-Pad11)") (class "Default")
      (node (ref "IC2") (pin "11") (pinfunction "Y4_11") (pintype "output"))
    )
    (net (code "94") (name "unconnected-(IC2A-Y5-Pad10)") (class "Default")
      (node (ref "IC2") (pin "10") (pinfunction "Y5_10") (pintype "output"))
    )
    (net (code "95") (name "unconnected-(IC2A-Y6-Pad9)") (class "Default")
      (node (ref "IC2") (pin "9") (pinfunction "Y6_9") (pintype "output"))
    )
    (net (code "96") (name "unconnected-(IC2A-Y7-Pad7)") (class "Default")
      (node (ref "IC2") (pin "7") (pinfunction "Y7_7") (pintype "output"))
    )
    (net (code "97") (name "unconnected-(JP1-Pad11)") (class "Default")
      (node (ref "JP1") (pin "11") (pinfunction "11_11") (pintype "passive"))
    )
    (net (code "98") (name "unconnected-(JP1-Pad19)") (class "Default")
      (node (ref "JP1") (pin "19") (pinfunction "19_19") (pintype "passive"))
    )
    (net (code "99") (name "unconnected-(U$2-NC-Pad1)") (class "Default")
      (node (ref "U$2") (pin "1") (pinfunction "NC_1") (pintype "bidirectional"))
    )
    (net (code "100") (name "unconnected-(U1-DTR-Pad11)") (class "Default")
      (node (ref "U1") (pin "11") (pinfunction "DTR_11") (pintype "output"))
    )
    (net (code "101") (name "unconnected-(U1-RXCLK-Pad5)") (class "Default")
      (node (ref "U1") (pin "5") (pinfunction "RXCLK_5") (pintype "bidirectional"))
    )
    (net (code "102") (name "unconnected-(U1-XTL2-Pad7)") (class "Default")
      (node (ref "U1") (pin "7") (pinfunction "XTL2_7") (pintype "output"))
    )
  )
)
